# sr_indicator_v0.net
KiCad netlist of a schematic drawn in EAGLE
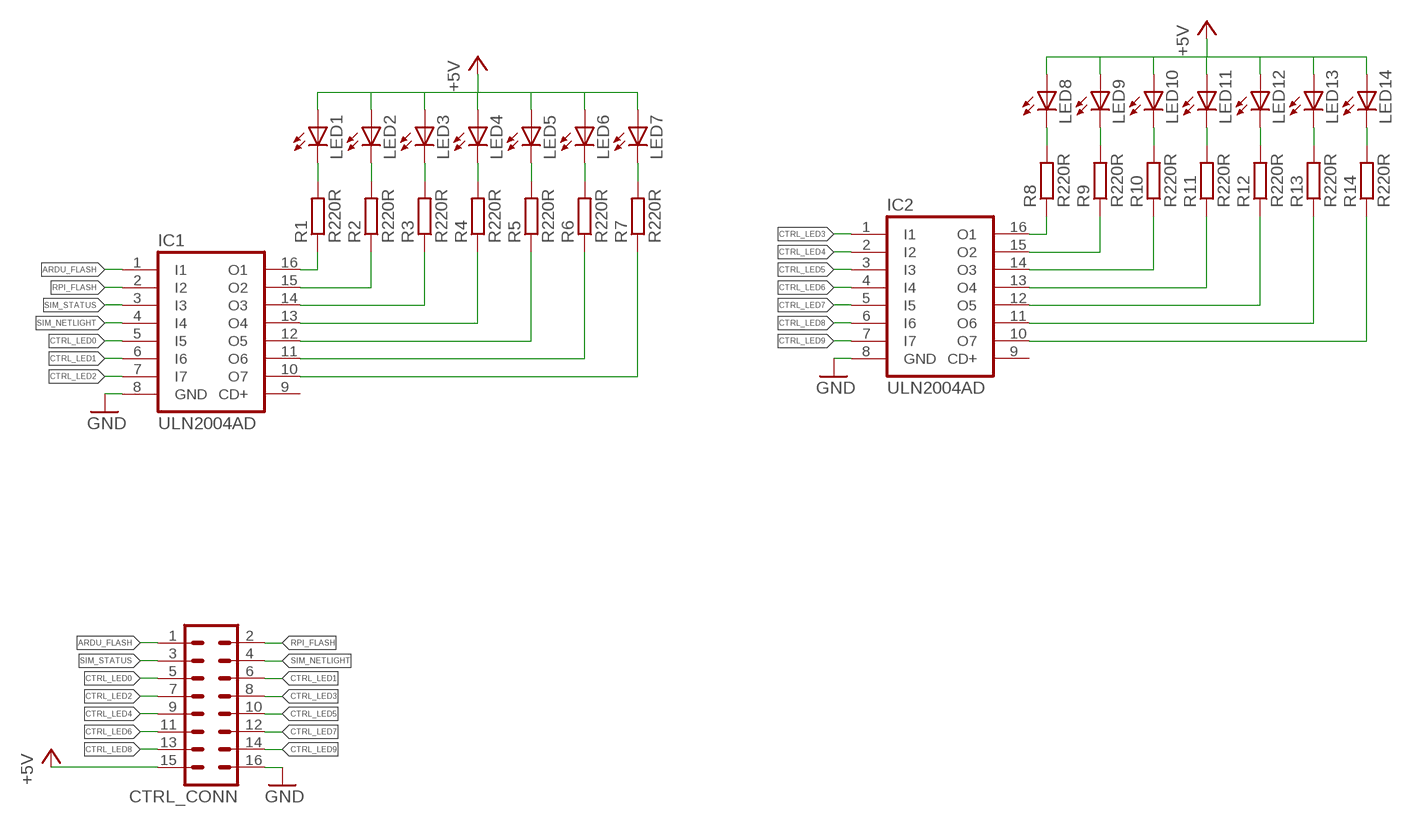
[diagram p0: schematic, sheet 1]

(export (version "E")
  (design (tool "Eeschema 10.0.6"))
  (components
    (comp (ref "CTRL_CONN")
      (value "MA08-2")
      (footprint "eagle-import:MA08-2")
      (libsource (lib "eagle-import") (part "MA08-2"))
    )
    (comp (ref "IC1")
      (value "ULN2004AD")
      (footprint "eagle-import:SO16")
      (libsource (lib "eagle-import") (part "ULN2004AD"))
    )
    (comp (ref "IC2")
      (value "ULN2004AD")
      (footprint "eagle-import:SO16")
      (libsource (lib "eagle-import") (part "ULN2004AD"))
    )
    (comp (ref "LED1")
      (value "LED3MM")
      (footprint "eagle-import:LED3MM")
      (libsource (lib "eagle-import") (part "LED3MM"))
    )
    (comp (ref "LED2")
      (value "LED3MM")
      (footprint "eagle-import:LED3MM")
      (libsource (lib "eagle-import") (part "LED3MM"))
    )
    (comp (ref "LED3")
      (value "LED3MM")
      (footprint "eagle-import:LED3MM")
      (libsource (lib "eagle-import") (part "LED3MM"))
    )
    (comp (ref "LED4")
      (value "LED3MM")
      (footprint "eagle-import:LED3MM")
      (libsource (lib "eagle-import") (part "LED3MM"))
    )
    (comp (ref "LED5")
      (value "LED3MM")
      (footprint "eagle-import:LED3MM")
      (libsource (lib "eagle-import") (part "LED3MM"))
    )
    (comp (ref "LED6")
      (value "LED3MM")
      (footprint "eagle-import:LED3MM")
      (libsource (lib "eagle-import") (part "LED3MM"))
    )
    (comp (ref "LED7")
      (value "LED3MM")
      (footprint "eagle-import:LED3MM")
      (libsource (lib "eagle-import") (part "LED3MM"))
    )
    (comp (ref "LED8")
      (value "LED3MM")
      (footprint "eagle-import:LED3MM")
      (libsource (lib "eagle-import") (part "LED3MM"))
    )
    (comp (ref "LED9")
      (value "LED3MM")
      (footprint "eagle-import:LED3MM")
      (libsource (lib "eagle-import") (part "LED3MM"))
    )
    (comp (ref "LED10")
      (value "LED3MM")
      (footprint "eagle-import:LED3MM")
      (libsource (lib "eagle-import") (part "LED3MM"))
    )
    (comp (ref "LED11")
      (value "LED3MM")
      (footprint "eagle-import:LED3MM")
      (libsource (lib "eagle-import") (part "LED3MM"))
    )
    (comp (ref "LED12")
      (value "LED3MM")
      (footprint "eagle-import:LED3MM")
      (libsource (lib "eagle-import") (part "LED3MM"))
    )
    (comp (ref "LED13")
      (value "LED3MM")
      (footprint "eagle-import:LED3MM")
      (libsource (lib "eagle-import") (part "LED3MM"))
    )
    (comp (ref "LED14")
      (value "LED3MM")
      (footprint "eagle-import:LED3MM")
      (libsource (lib "eagle-import") (part "LED3MM"))
    )
    (comp (ref "R1")
      (value "R220R")
      (footprint "eagle-import:M0805")
      (libsource (lib "eagle-import") (part "R-EU_M0805"))
    )
    (comp (ref "R2")
      (value "R220R")
      (footprint "eagle-import:M0805")
      (libsource (lib "eagle-import") (part "R-EU_M0805"))
    )
    (comp (ref "R3")
      (value "R220R")
      (footprint "eagle-import:M0805")
      (libsource (lib "eagle-import") (part "R-EU_M0805"))
    )
    (comp (ref "R4")
      (value "R220R")
      (footprint "eagle-import:M0805")
      (libsource (lib "eagle-import") (part "R-EU_M0805"))
    )
    (comp (ref "R5")
      (value "R220R")
      (footprint "eagle-import:M0805")
      (libsource (lib "eagle-import") (part "R-EU_M0805"))
    )
    (comp (ref "R6")
      (value "R220R")
      (footprint "eagle-import:M0805")
      (libsource (lib "eagle-import") (part "R-EU_M0805"))
    )
    (comp (ref "R7")
      (value "R220R")
      (footprint "eagle-import:M0805")
      (libsource (lib "eagle-import") (part "R-EU_M0805"))
    )
    (comp (ref "R8")
      (value "R220R")
      (footprint "eagle-import:M0805")
      (libsource (lib "eagle-import") (part "R-EU_M0805"))
    )
    (comp (ref "R9")
      (value "R220R")
      (footprint "eagle-import:M0805")
      (libsource (lib "eagle-import") (part "R-EU_M0805"))
    )
    (comp (ref "R10")
      (value "R220R")
      (footprint "eagle-import:M0805")
      (libsource (lib "eagle-import") (part "R-EU_M0805"))
    )
    (comp (ref "R11")
      (value "R220R")
      (footprint "eagle-import:M0805")
      (libsource (lib "eagle-import") (part "R-EU_M0805"))
    )
    (comp (ref "R12")
      (value "R220R")
      (footprint "eagle-import:M0805")
      (libsource (lib "eagle-import") (part "R-EU_M0805"))
    )
    (comp (ref "R13")
      (value "R220R")
      (footprint "eagle-import:M0805")
      (libsource (lib "eagle-import") (part "R-EU_M0805"))
    )
    (comp (ref "R14")
      (value "R220R")
      (footprint "eagle-import:M0805")
      (libsource (lib "eagle-import") (part "R-EU_M0805"))
    )
  )
  (nets
    (net (code "1") (name "+5V") (class "Default")
      (node (ref "CTRL_CONN") (pin "15") (pinfunction "15_15") (pintype "passive"))
      (node (ref "LED1") (pin "A") (pinfunction "A_A") (pintype "passive"))
      (node (ref "LED10") (pin "A") (pinfunction "A_A") (pintype "passive"))
      (node (ref "LED11") (pin "A") (pinfunction "A_A") (pintype "passive"))
      (node (ref "LED12") (pin "A") (pinfunction "A_A") (pintype "passive"))
      (node (ref "LED13") (pin "A") (pinfunction "A_A") (pintype "passive"))
      (node (ref "LED14") (pin "A") (pinfunction "A_A") (pintype "passive"))
      (node (ref "LED2") (pin "A") (pinfunction "A_A") (pintype "passive"))
      (node (ref "LED3") (pin "A") (pinfunction "A_A") (pintype "passive"))
      (node (ref "LED4") (pin "A") (pinfunction "A_A") (pintype "passive"))
      (node (ref "LED5") (pin "A") (pinfunction "A_A") (pintype "passive"))
      (node (ref "LED6") (pin "A") (pinfunction "A_A") (pintype "passive"))
      (node (ref "LED7") (pin "A") (pinfunction "A_A") (pintype "passive"))
      (node (ref "LED8") (pin "A") (pinfunction "A_A") (pintype "passive"))
      (node (ref "LED9") (pin "A") (pinfunction "A_A") (pintype "passive"))
    )
    (net (code "2") (name "ARDU_FLASH") (class "Default")
      (node (ref "CTRL_CONN") (pin "1") (pinfunction "1_1") (pintype "passive"))
      (node (ref "IC1") (pin "1") (pinfunction "I1_1") (pintype "input"))
    )
    (net (code "3") (name "CTRL_LED0") (class "Default")
      (node (ref "CTRL_CONN") (pin "5") (pinfunction "5_5") (pintype "passive"))
      (node (ref "IC1") (pin "5") (pinfunction "I5_5") (pintype "input"))
    )
    (net (code "4") (name "CTRL_LED1") (class "Default")
      (node (ref "CTRL_CONN") (pin "6") (pinfunction "6_6") (pintype "passive"))
      (node (ref "IC1") (pin "6") (pinfunction "I6_6") (pintype "input"))
    )
    (net (code "5") (name "CTRL_LED2") (class "Default")
      (node (ref "CTRL_CONN") (pin "7") (pinfunction "7_7") (pintype "passive"))
      (node (ref "IC1") (pin "7") (pinfunction "I7_7") (pintype "input"))
    )
    (net (code "6") (name "CTRL_LED3") (class "Default")
      (node (ref "CTRL_CONN") (pin "8") (pinfunction "8_8") (pintype "passive"))
      (node (ref "IC2") (pin "1") (pinfunction "I1_1") (pintype "input"))
    )
    (net (code "7") (name "CTRL_LED4") (class "Default")
      (node (ref "CTRL_CONN") (pin "9") (pinfunction "9_9") (pintype "passive"))
      (node (ref "IC2") (pin "2") (pinfunction "I2_2") (pintype "input"))
    )
    (net (code "8") (name "CTRL_LED5") (class "Default")
      (node (ref "CTRL_CONN") (pin "10") (pinfunction "10_10") (pintype "passive"))
      (node (ref "IC2") (pin "3") (pinfunction "I3_3") (pintype "input"))
    )
    (net (code "9") (name "CTRL_LED6") (class "Default")
      (node (ref "CTRL_CONN") (pin "11") (pinfunction "11_11") (pintype "passive"))
      (node (ref "IC2") (pin "4") (pinfunction "I4_4") (pintype "input"))
    )
    (net (code "10") (name "CTRL_LED7") (class "Default")
      (node (ref "CTRL_CONN") (pin "12") (pinfunction "12_12") (pintype "passive"))
      (node (ref "IC2") (pin "5") (pinfunction "I5_5") (pintype "input"))
    )
    (net (code "11") (name "CTRL_LED8") (class "Default")
      (node (ref "CTRL_CONN") (pin "13") (pinfunction "13_13") (pintype "passive"))
      (node (ref "IC2") (pin "6") (pinfunction "I6_6") (pintype "input"))
    )
    (net (code "12") (name "CTRL_LED9") (class "Default")
      (node (ref "CTRL_CONN") (pin "14") (pinfunction "14_14") (pintype "passive"))
      (node (ref "IC2") (pin "7") (pinfunction "I7_7") (pintype "input"))
    )
    (net (code "13") (name "GND") (class "Default")
      (node (ref "CTRL_CONN") (pin "16") (pinfunction "16_16") (pintype "passive"))
      (node (ref "IC1") (pin "8") (pinfunction "GND_8") (pintype "power_in"))
      (node (ref "IC2") (pin "8") (pinfunction "GND_8") (pintype "power_in"))
    )
    (net (code "14") (name "Net-(IC1-O1)") (class "Default")
      (node (ref "IC1") (pin "16") (pinfunction "O1_16") (pintype "open_collector"))
      (node (ref "R1") (pin "1") (pinfunction "1_1") (pintype "passive"))
    )
    (net (code "15") (name "Net-(IC1-O2)") (class "Default")
      (node (ref "IC1") (pin "15") (pinfunction "O2_15") (pintype "open_collector"))
      (node (ref "R2") (pin "1") (pinfunction "1_1") (pintype "passive"))
    )
    (net (code "16") (name "Net-(IC1-O3)") (class "Default")
      (node (ref "IC1") (pin "14") (pinfunction "O3_14") (pintype "open_collector"))
      (node (ref "R3") (pin "1") (pinfunction "1_1") (pintype "passive"))
    )
    (net (code "17") (name "Net-(IC1-O4)") (class "Default")
      (node (ref "IC1") (pin "13") (pinfunction "O4_13") (pintype "open_collector"))
      (node (ref "R4") (pin "1") (pinfunction "1_1") (pintype "passive"))
    )
    (net (code "18") (name "Net-(IC1-O5)") (class "Default")
      (node (ref "IC1") (pin "12") (pinfunction "O5_12") (pintype "open_collector"))
      (node (ref "R5") (pin "1") (pinfunction "1_1") (pintype "passive"))
    )
    (net (code "19") (name "Net-(IC1-O6)") (class "Default")
      (node (ref "IC1") (pin "11") (pinfunction "O6_11") (pintype "open_collector"))
      (node (ref "R6") (pin "1") (pinfunction "1_1") (pintype "passive"))
    )
    (net (code "20") (name "Net-(IC1-O7)") (class "Default")
      (node (ref "IC1") (pin "10") (pinfunction "O7_10") (pintype "open_collector"))
      (node (ref "R7") (pin "1") (pinfunction "1_1") (pintype "passive"))
    )
    (net (code "21") (name "Net-(IC2-O1)") (class "Default")
      (node (ref "IC2") (pin "16") (pinfunction "O1_16") (pintype "open_collector"))
      (node (ref "R8") (pin "1") (pinfunction "1_1") (pintype "passive"))
    )
    (net (code "22") (name "Net-(IC2-O2)") (class "Default")
      (node (ref "IC2") (pin "15") (pinfunction "O2_15") (pintype "open_collector"))
      (node (ref "R9") (pin "1") (pinfunction "1_1") (pintype "passive"))
    )
    (net (code "23") (name "Net-(IC2-O3)") (class "Default")
      (node (ref "IC2") (pin "14") (pinfunction "O3_14") (pintype "open_collector"))
      (node (ref "R10") (pin "1") (pinfunction "1_1") (pintype "passive"))
    )
    (net (code "24") (name "Net-(IC2-O4)") (class "Default")
      (node (ref "IC2") (pin "13") (pinfunction "O4_13") (pintype "open_collector"))
      (node (ref "R11") (pin "1") (pinfunction "1_1") (pintype "passive"))
    )
    (net (code "25") (name "Net-(IC2-O5)") (class "Default")
      (node (ref "IC2") (pin "12") (pinfunction "O5_12") (pintype "open_collector"))
      (node (ref "R12") (pin "1") (pinfunction "1_1") (pintype "passive"))
    )
    (net (code "26") (name "Net-(IC2-O6)") (class "Default")
      (node (ref "IC2") (pin "11") (pinfunction "O6_11") (pintype "open_collector"))
      (node (ref "R13") (pin "1") (pinfunction "1_1") (pintype "passive"))
    )
    (net (code "27") (name "Net-(IC2-O7)") (class "Default")
      (node (ref "IC2") (pin "10") (pinfunction "O7_10") (pintype "open_collector"))
      (node (ref "R14") (pin "1") (pinfunction "1_1") (pintype "passive"))
    )
    (net (code "28") (name "Net-(LED1-C)") (class "Default")
      (node (ref "LED1") (pin "K") (pinfunction "C_K") (pintype "passive"))
      (node (ref "R1") (pin "2") (pinfunction "2_2") (pintype "passive"))
    )
    (net (code "29") (name "Net-(LED2-C)") (class "Default")
      (node (ref "LED2") (pin "K") (pinfunction "C_K") (pintype "passive"))
      (node (ref "R2") (pin "2") (pinfunction "2_2") (pintype "passive"))
    )
    (net (code "30") (name "Net-(LED3-C)") (class "Default")
      (node (ref "LED3") (pin "K") (pinfunction "C_K") (pintype "passive"))
      (node (ref "R3") (pin "2") (pinfunction "2_2") (pintype "passive"))
    )
    (net (code "31") (name "Net-(LED4-C)") (class "Default")
      (node (ref "LED4") (pin "K") (pinfunction "C_K") (pintype "passive"))
      (node (ref "R4") (pin "2") (pinfunction "2_2") (pintype "passive"))
    )
    (net (code "32") (name "Net-(LED5-C)") (class "Default")
      (node (ref "LED5") (pin "K") (pinfunction "C_K") (pintype "passive"))
      (node (ref "R5") (pin "2") (pinfunction "2_2") (pintype "passive"))
    )
    (net (code "33") (name "Net-(LED6-C)") (class "Default")
      (node (ref "LED6") (pin "K") (pinfunction "C_K") (pintype "passive"))
      (node (ref "R6") (pin "2") (pinfunction "2_2") (pintype "passive"))
    )
    (net (code "34") (name "Net-(LED7-C)") (class "Default")
      (node (ref "LED7") (pin "K") (pinfunction "C_K") (pintype "passive"))
      (node (ref "R7") (pin "2") (pinfunction "2_2") (pintype "passive"))
    )
    (net (code "35") (name "Net-(LED8-C)") (class "Default")
      (node (ref "LED8") (pin "K") (pinfunction "C_K") (pintype "passive"))
      (node (ref "R8") (pin "2") (pinfunction "2_2") (pintype "passive"))
    )
    (net (code "36") (name "Net-(LED9-C)") (class "Default")
      (node (ref "LED9") (pin "K") (pinfunction "C_K") (pintype "passive"))
      (node (ref "R9") (pin "2") (pinfunction "2_2") (pintype "passive"))
    )
    (net (code "37") (name "Net-(LED10-C)") (class "Default")
      (node (ref "LED10") (pin "K") (pinfunction "C_K") (pintype "passive"))
      (node (ref "R10") (pin "2") (pinfunction "2_2") (pintype "passive"))
    )
    (net (code "38") (name "Net-(LED11-C)") (class "Default")
      (node (ref "LED11") (pin "K") (pinfunction "C_K") (pintype "passive"))
      (node (ref "R11") (pin "2") (pinfunction "2_2") (pintype "passive"))
    )
    (net (code "39") (name "Net-(LED12-C)") (class "Default")
      (node (ref "LED12") (pin "K") (pinfunction "C_K") (pintype "passive"))
      (node (ref "R12") (pin "2") (pinfunction "2_2") (pintype "passive"))
    )
    (net (code "40") (name "Net-(LED13-C)") (class "Default")
      (node (ref "LED13") (pin "K") (pinfunction "C_K") (pintype "passive"))
      (node (ref "R13") (pin "2") (pinfunction "2_2") (pintype "passive"))
    )
    (net (code "41") (name "Net-(LED14-C)") (class "Default")
      (node (ref "LED14") (pin "K") (pinfunction "C_K") (pintype "passive"))
      (node (ref "R14") (pin "2") (pinfunction "2_2") (pintype "passive"))
    )
    (net (code "42") (name "RPI_FLASH") (class "Default")
      (node (ref "CTRL_CONN") (pin "2") (pinfunction "2_2") (pintype "passive"))
      (node (ref "IC1") (pin "2") (pinfunction "I2_2") (pintype "input"))
    )
    (net (code "43") (name "SIM_NETLIGHT") (class "Default")
      (node (ref "CTRL_CONN") (pin "4") (pinfunction "4_4") (pintype "passive"))
      (node (ref "IC1") (pin "4") (pinfunction "I4_4") (pintype "input"))
    )
    (net (code "44") (name "SIM_STATUS") (class "Default")
      (node (ref "CTRL_CONN") (pin "3") (pinfunction "3_3") (pintype "passive"))
      (node (ref "IC1") (pin "3") (pinfunction "I3_3") (pintype "input"))
    )
    (net (code "45") (name "unconnected-(IC1-CD+-Pad9)") (class "Default")
      (node (ref "IC1") (pin "9") (pinfunction "CD+_9") (pintype "passive"))
    )
    (net (code "46") (name "unconnected-(IC2-CD+-Pad9)") (class "Default")
      (node (ref "IC2") (pin "9") (pinfunction "CD+_9") (pintype "passive"))
    )
  )
)
